# ledboard.net
KiCad netlist of a schematic drawn in EAGLE
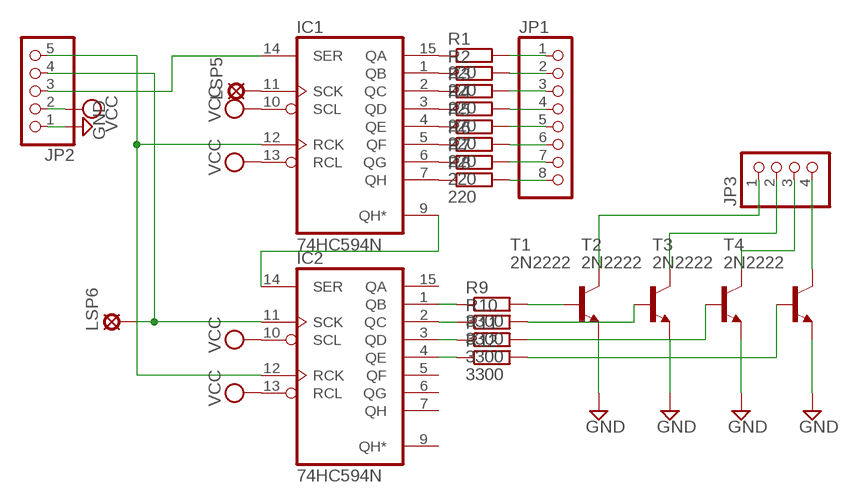
[diagram p0: schematic, sheet 1]

(export (version "E")
  (design (tool "Eeschema 10.0.6"))
  (components
    (comp (ref "IC1")
      (value "74HC594N")
      (footprint "eagle-import:DIL16")
      (libsource (lib "eagle-import") (part "74594NHC"))
    )
    (comp (ref "IC2")
      (value "74HC594N")
      (footprint "eagle-import:DIL16")
      (libsource (lib "eagle-import") (part "74594NHC"))
    )
    (comp (ref "JP1")
      (value "PINHD-1X8")
      (footprint "eagle-import:1X08")
      (libsource (lib "eagle-import") (part "PINHD-1X8"))
    )
    (comp (ref "JP2")
      (value "PINHD-1X5")
      (footprint "eagle-import:1X05")
      (libsource (lib "eagle-import") (part "PINHD-1X5"))
    )
    (comp (ref "JP3")
      (value "PINHD-1X4")
      (footprint "eagle-import:1X04")
      (libsource (lib "eagle-import") (part "PINHD-1X4"))
    )
    (comp (ref "LSP5")
      (value "LSP10")
      (footprint "eagle-import:LSP10")
      (libsource (lib "eagle-import") (part "LSP10"))
    )
    (comp (ref "LSP6")
      (value "LSP10")
      (footprint "eagle-import:LSP10")
      (libsource (lib "eagle-import") (part "LSP10"))
    )
    (comp (ref "R1")
      (value "220")
      (footprint "eagle-import:0207_10")
      (libsource (lib "eagle-import") (part "R-EU_0207/10"))
    )
    (comp (ref "R2")
      (value "220")
      (footprint "eagle-import:0207_10")
      (libsource (lib "eagle-import") (part "R-EU_0207/10"))
    )
    (comp (ref "R3")
      (value "220")
      (footprint "eagle-import:0207_10")
      (libsource (lib "eagle-import") (part "R-EU_0207/10"))
    )
    (comp (ref "R4")
      (value "220")
      (footprint "eagle-import:0207_10")
      (libsource (lib "eagle-import") (part "R-EU_0207/10"))
    )
    (comp (ref "R5")
      (value "220")
      (footprint "eagle-import:0207_10")
      (libsource (lib "eagle-import") (part "R-EU_0207/10"))
    )
    (comp (ref "R6")
      (value "220")
      (footprint "eagle-import:0207_10")
      (libsource (lib "eagle-import") (part "R-EU_0207/10"))
    )
    (comp (ref "R7")
      (value "220")
      (footprint "eagle-import:0207_10")
      (libsource (lib "eagle-import") (part "R-EU_0207/10"))
    )
    (comp (ref "R8")
      (value "220")
      (footprint "eagle-import:0207_10")
      (libsource (lib "eagle-import") (part "R-EU_0207/10"))
    )
    (comp (ref "R9")
      (value "3300")
      (footprint "eagle-import:0207_10")
      (libsource (lib "eagle-import") (part "R-EU_0207/10"))
    )
    (comp (ref "R10")
      (value "3300")
      (footprint "eagle-import:0207_10")
      (libsource (lib "eagle-import") (part "R-EU_0207/10"))
    )
    (comp (ref "R11")
      (value "3300")
      (footprint "eagle-import:0207_10")
      (libsource (lib "eagle-import") (part "R-EU_0207/10"))
    )
    (comp (ref "R12")
      (value "3300")
      (footprint "eagle-import:0207_10")
      (libsource (lib "eagle-import") (part "R-EU_0207/10"))
    )
    (comp (ref "T1")
      (value "2N2222")
      (footprint "eagle-import:TO92-EBC-OVAL")
      (libsource (lib "eagle-import") (part "2N2222"))
    )
    (comp (ref "T2")
      (value "2N2222")
      (footprint "eagle-import:TO92-EBC-OVAL")
      (libsource (lib "eagle-import") (part "2N2222"))
    )
    (comp (ref "T3")
      (value "2N2222")
      (footprint "eagle-import:TO92-EBC-OVAL")
      (libsource (lib "eagle-import") (part "2N2222"))
    )
    (comp (ref "T4")
      (value "2N2222")
      (footprint "eagle-import:TO92-EBC-OVAL")
      (libsource (lib "eagle-import") (part "2N2222"))
    )
  )
  (nets
    (net (code "1") (name "GND") (class "Default")
      (node (ref "JP2") (pin "1") (pinfunction "1_1") (pintype "passive"))
      (node (ref "T1") (pin "E") (pinfunction "E_E") (pintype "passive"))
      (node (ref "T2") (pin "E") (pinfunction "E_E") (pintype "passive"))
      (node (ref "T3") (pin "E") (pinfunction "E_E") (pintype "passive"))
      (node (ref "T4") (pin "E") (pinfunction "E_E") (pintype "passive"))
    )
    (net (code "2") (name "Net-(IC1A-QA)") (class "Default")
      (node (ref "IC1") (pin "15") (pinfunction "QA_15") (pintype "output"))
      (node (ref "R1") (pin "1") (pinfunction "1_1") (pintype "passive"))
    )
    (net (code "3") (name "Net-(IC1A-QB)") (class "Default")
      (node (ref "IC1") (pin "1") (pinfunction "QB_1") (pintype "output"))
      (node (ref "R2") (pin "1") (pinfunction "1_1") (pintype "passive"))
    )
    (net (code "4") (name "Net-(IC1A-QC)") (class "Default")
      (node (ref "IC1") (pin "2") (pinfunction "QC_2") (pintype "output"))
      (node (ref "R3") (pin "1") (pinfunction "1_1") (pintype "passive"))
    )
    (net (code "5") (name "Net-(IC1A-QD)") (class "Default")
      (node (ref "IC1") (pin "3") (pinfunction "QD_3") (pintype "output"))
      (node (ref "R4") (pin "1") (pinfunction "1_1") (pintype "passive"))
    )
    (net (code "6") (name "Net-(IC1A-QE)") (class "Default")
      (node (ref "IC1") (pin "4") (pinfunction "QE_4") (pintype "output"))
      (node (ref "R5") (pin "1") (pinfunction "1_1") (pintype "passive"))
    )
    (net (code "7") (name "Net-(IC1A-QF)") (class "Default")
      (node (ref "IC1") (pin "5") (pinfunction "QF_5") (pintype "output"))
      (node (ref "R6") (pin "1") (pinfunction "1_1") (pintype "passive"))
    )
    (net (code "8") (name "Net-(IC1A-QG)") (class "Default")
      (node (ref "IC1") (pin "6") (pinfunction "QG_6") (pintype "output"))
      (node (ref "R7") (pin "1") (pinfunction "1_1") (pintype "passive"))
    )
    (net (code "9") (name "Net-(IC1A-QH)") (class "Default")
      (node (ref "IC1") (pin "7") (pinfunction "QH_7") (pintype "output"))
      (node (ref "R8") (pin "1") (pinfunction "1_1") (pintype "passive"))
    )
    (net (code "10") (name "Net-(IC1A-QH*)") (class "Default")
      (node (ref "IC1") (pin "9") (pinfunction "QH*_9") (pintype "output"))
      (node (ref "IC2") (pin "14") (pinfunction "SER_14") (pintype "input"))
    )
    (net (code "11") (name "Net-(IC1A-RCK)") (class "Default")
      (node (ref "IC1") (pin "12") (pinfunction "RCK_12") (pintype "input"))
      (node (ref "IC2") (pin "12") (pinfunction "RCK_12") (pintype "input"))
      (node (ref "JP2") (pin "5") (pinfunction "5_5") (pintype "passive"))
    )
    (net (code "12") (name "Net-(IC1A-SCK)") (class "Default")
      (node (ref "IC1") (pin "11") (pinfunction "SCK_11") (pintype "input"))
      (node (ref "LSP5") (pin "MP") (pinfunction "MP_MP") (pintype "passive"))
    )
    (net (code "13") (name "Net-(IC1A-SER)") (class "Default")
      (node (ref "IC1") (pin "14") (pinfunction "SER_14") (pintype "input"))
      (node (ref "JP2") (pin "3") (pinfunction "3_3") (pintype "passive"))
    )
    (net (code "14") (name "Net-(IC2A-QB)") (class "Default")
      (node (ref "IC2") (pin "1") (pinfunction "QB_1") (pintype "output"))
      (node (ref "R9") (pin "1") (pinfunction "1_1") (pintype "passive"))
    )
    (net (code "15") (name "Net-(IC2A-QC)") (class "Default")
      (node (ref "IC2") (pin "2") (pinfunction "QC_2") (pintype "output"))
      (node (ref "R10") (pin "1") (pinfunction "1_1") (pintype "passive"))
    )
    (net (code "16") (name "Net-(IC2A-QD)") (class "Default")
      (node (ref "IC2") (pin "3") (pinfunction "QD_3") (pintype "output"))
      (node (ref "R11") (pin "1") (pinfunction "1_1") (pintype "passive"))
    )
    (net (code "17") (name "Net-(IC2A-QE)") (class "Default")
      (node (ref "IC2") (pin "4") (pinfunction "QE_4") (pintype "output"))
      (node (ref "R12") (pin "1") (pinfunction "1_1") (pintype "passive"))
    )
    (net (code "18") (name "Net-(IC2A-SCK)") (class "Default")
      (node (ref "IC2") (pin "11") (pinfunction "SCK_11") (pintype "input"))
      (node (ref "JP2") (pin "4") (pinfunction "4_4") (pintype "passive"))
      (node (ref "LSP6") (pin "MP") (pinfunction "MP_MP") (pintype "passive"))
    )
    (net (code "19") (name "Net-(JP1-Pad1)") (class "Default")
      (node (ref "JP1") (pin "1") (pinfunction "1_1") (pintype "passive"))
      (node (ref "R1") (pin "2") (pinfunction "2_2") (pintype "passive"))
    )
    (net (code "20") (name "Net-(JP1-Pad2)") (class "Default")
      (node (ref "JP1") (pin "2") (pinfunction "2_2") (pintype "passive"))
      (node (ref "R2") (pin "2") (pinfunction "2_2") (pintype "passive"))
    )
    (net (code "21") (name "Net-(JP1-Pad3)") (class "Default")
      (node (ref "JP1") (pin "3") (pinfunction "3_3") (pintype "passive"))
      (node (ref "R3") (pin "2") (pinfunction "2_2") (pintype "passive"))
    )
    (net (code "22") (name "Net-(JP1-Pad4)") (class "Default")
      (node (ref "JP1") (pin "4") (pinfunction "4_4") (pintype "passive"))
      (node (ref "R4") (pin "2") (pinfunction "2_2") (pintype "passive"))
    )
    (net (code "23") (name "Net-(JP1-Pad5)") (class "Default")
      (node (ref "JP1") (pin "5") (pinfunction "5_5") (pintype "passive"))
      (node (ref "R5") (pin "2") (pinfunction "2_2") (pintype "passive"))
    )
    (net (code "24") (name "Net-(JP1-Pad6)") (class "Default")
      (node (ref "JP1") (pin "6") (pinfunction "6_6") (pintype "passive"))
      (node (ref "R6") (pin "2") (pinfunction "2_2") (pintype "passive"))
    )
    (net (code "25") (name "Net-(JP1-Pad7)") (class "Default")
      (node (ref "JP1") (pin "7") (pinfunction "7_7") (pintype "passive"))
      (node (ref "R7") (pin "2") (pinfunction "2_2") (pintype "passive"))
    )
    (net (code "26") (name "Net-(JP1-Pad8)") (class "Default")
      (node (ref "JP1") (pin "8") (pinfunction "8_8") (pintype "passive"))
      (node (ref "R8") (pin "2") (pinfunction "2_2") (pintype "passive"))
    )
    (net (code "27") (name "Net-(JP3-Pad1)") (class "Default")
      (node (ref "JP3") (pin "1") (pinfunction "1_1") (pintype "passive"))
      (node (ref "T1") (pin "C") (pinfunction "C_C") (pintype "passive"))
    )
    (net (code "28") (name "Net-(JP3-Pad2)") (class "Default")
      (node (ref "JP3") (pin "2") (pinfunction "2_2") (pintype "passive"))
      (node (ref "T2") (pin "C") (pinfunction "C_C") (pintype "passive"))
    )
    (net (code "29") (name "Net-(JP3-Pad3)") (class "Default")
      (node (ref "JP3") (pin "3") (pinfunction "3_3") (pintype "passive"))
      (node (ref "T3") (pin "C") (pinfunction "C_C") (pintype "passive"))
    )
    (net (code "30") (name "Net-(JP3-Pad4)") (class "Default")
      (node (ref "JP3") (pin "4") (pinfunction "4_4") (pintype "passive"))
      (node (ref "T4") (pin "C") (pinfunction "C_C") (pintype "passive"))
    )
    (net (code "31") (name "Net-(R9-Pad2)") (class "Default")
      (node (ref "R9") (pin "2") (pinfunction "2_2") (pintype "passive"))
      (node (ref "T1") (pin "B") (pinfunction "B_B") (pintype "passive"))
    )
    (net (code "32") (name "Net-(R10-Pad2)") (class "Default")
      (node (ref "R10") (pin "2") (pinfunction "2_2") (pintype "passive"))
      (node (ref "T2") (pin "B") (pinfunction "B_B") (pintype "passive"))
    )
    (net (code "33") (name "Net-(R11-Pad2)") (class "Default")
      (node (ref "R11") (pin "2") (pinfunction "2_2") (pintype "passive"))
      (node (ref "T3") (pin "B") (pinfunction "B_B") (pintype "passive"))
    )
    (net (code "34") (name "Net-(R12-Pad2)") (class "Default")
      (node (ref "R12") (pin "2") (pinfunction "2_2") (pintype "passive"))
      (node (ref "T4") (pin "B") (pinfunction "B_B") (pintype "passive"))
    )
    (net (code "35") (name "VCC") (class "Default")
      (node (ref "IC1") (pin "10") (pinfunction "SCL_10") (pintype "input"))
      (node (ref "IC1") (pin "13") (pinfunction "RCL_13") (pintype "input"))
      (node (ref "IC2") (pin "10") (pinfunction "SCL_10") (pintype "input"))
      (node (ref "IC2") (pin "13") (pinfunction "RCL_13") (pintype "input"))
      (node (ref "JP2") (pin "2") (pinfunction "2_2") (pintype "passive"))
    )
    (net (code "36") (name "unconnected-(IC2A-QA-Pad15)") (class "Default")
      (node (ref "IC2") (pin "15") (pinfunction "QA_15") (pintype "output"))
    )
    (net (code "37") (name "unconnected-(IC2A-QF-Pad5)") (class "Default")
      (node (ref "IC2") (pin "5") (pinfunction "QF_5") (pintype "output"))
    )
    (net (code "38") (name "unconnected-(IC2A-QG-Pad6)") (class "Default")
      (node (ref "IC2") (pin "6") (pinfunction "QG_6") (pintype "output"))
    )
    (net (code "39") (name "unconnected-(IC2A-QH*-Pad9)") (class "Default")
      (node (ref "IC2") (pin "9") (pinfunction "QH*_9") (pintype "output"))
    )
    (net (code "40") (name "unconnected-(IC2A-QH-Pad7)") (class "Default")
      (node (ref "IC2") (pin "7") (pinfunction "QH_7") (pintype "output"))
    )
  )
)
